# I2C.net
KiCad netlist of a schematic drawn in EAGLE
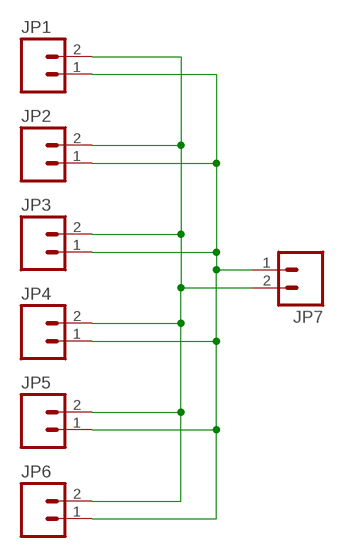
[diagram p0: schematic, sheet 1]

(export (version "E")
  (design (tool "Eeschema 10.0.6"))
  (components
    (comp (ref "JP1")
      (value "M02PTH")
      (footprint "eagle-import:1X02")
      (libsource (lib "eagle-import") (part "M02PTH"))
    )
    (comp (ref "JP2")
      (value "M02PTH")
      (footprint "eagle-import:1X02")
      (libsource (lib "eagle-import") (part "M02PTH"))
    )
    (comp (ref "JP3")
      (value "M02PTH")
      (footprint "eagle-import:1X02")
      (libsource (lib "eagle-import") (part "M02PTH"))
    )
    (comp (ref "JP4")
      (value "M02PTH")
      (footprint "eagle-import:1X02")
      (libsource (lib "eagle-import") (part "M02PTH"))
    )
    (comp (ref "JP5")
      (value "M02PTH")
      (footprint "eagle-import:1X02")
      (libsource (lib "eagle-import") (part "M02PTH"))
    )
    (comp (ref "JP6")
      (value "M02PTH")
      (footprint "eagle-import:1X02")
      (libsource (lib "eagle-import") (part "M02PTH"))
    )
    (comp (ref "JP7")
      (value "M02PTH")
      (footprint "eagle-import:1X02")
      (libsource (lib "eagle-import") (part "M02PTH"))
    )
  )
  (nets
    (net (code "1") (name "Net-(JP1-Pad1)") (class "Default")
      (node (ref "JP1") (pin "1") (pinfunction "1_1") (pintype "passive"))
      (node (ref "JP2") (pin "1") (pinfunction "1_1") (pintype "passive"))
      (node (ref "JP3") (pin "1") (pinfunction "1_1") (pintype "passive"))
      (node (ref "JP4") (pin "1") (pinfunction "1_1") (pintype "passive"))
      (node (ref "JP5") (pin "1") (pinfunction "1_1") (pintype "passive"))
      (node (ref "JP6") (pin "1") (pinfunction "1_1") (pintype "passive"))
      (node (ref "JP7") (pin "1") (pinfunction "1_1") (pintype "passive"))
    )
    (net (code "2") (name "Net-(JP1-Pad2)") (class "Default")
      (node (ref "JP1") (pin "2") (pinfunction "2_2") (pintype "passive"))
      (node (ref "JP2") (pin "2") (pinfunction "2_2") (pintype "passive"))
      (node (ref "JP3") (pin "2") (pinfunction "2_2") (pintype "passive"))
      (node (ref "JP4") (pin "2") (pinfunction "2_2") (pintype "passive"))
      (node (ref "JP5") (pin "2") (pinfunction "2_2") (pintype "passive"))
      (node (ref "JP6") (pin "2") (pinfunction "2_2") (pintype "passive"))
      (node (ref "JP7") (pin "2") (pinfunction "2_2") (pintype "passive"))
    )
  )
)
